# Sema.net
KiCad netlist of a schematic drawn in Altium Designer
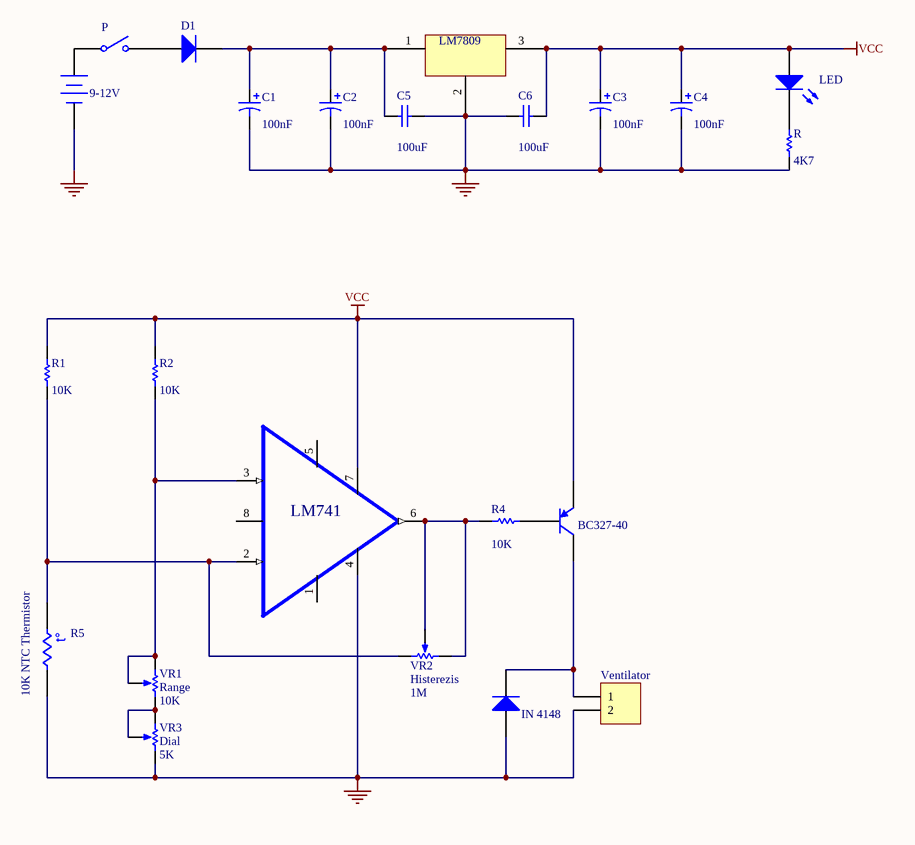
[diagram p0: Sema.SchDoc]

(export (version "E")
  (design (tool "Eeschema 10.0.6"))
  (components
    (comp (ref "9V")
      (value "9-12V")
      (footprint "BAT-2")
      (description "Multicell Battery")
      (fields (field (name "PUBLISHER") "Altium Limited"))
      (libsource (lib "Miscellaneous Devices") (part "Battery"))
    )
    (comp (ref "C1")
      (value "100nF")
      (footprint "CAPPRD350W60D800H1150:CAPPRD350W60D800H1150")
      (description "Polarized Capacitor (Radial)")
      (fields (field (name "Comment") "Cap Pol1") (field (name "PUBLISHER") "Altium Limited"))
      (libsource (lib "Miscellaneous Devices") (part "Cap Pol1"))
    )
    (comp (ref "C2")
      (value "100nF")
      (footprint "CAPPRD350W60D800H1150:CAPPRD350W60D800H1150")
      (description "Polarized Capacitor (Radial)")
      (fields (field (name "Comment") "Cap Pol1") (field (name "PUBLISHER") "Altium Limited"))
      (libsource (lib "Miscellaneous Devices") (part "Cap Pol1"))
    )
    (comp (ref "C3")
      (value "100nF")
      (footprint "CAPPRD350W60D800H1150:CAPPRD350W60D800H1150")
      (description "Polarized Capacitor (Radial)")
      (fields (field (name "Comment") "Cap Pol1") (field (name "PUBLISHER") "Altium Limited"))
      (libsource (lib "Miscellaneous Devices") (part "Cap Pol1"))
    )
    (comp (ref "C4")
      (value "100nF")
      (footprint "CAPPRD350W60D800H1150:CAPPRD350W60D800H1150")
      (description "Polarized Capacitor (Radial)")
      (fields (field (name "Comment") "Cap Pol1") (field (name "PUBLISHER") "Altium Limited"))
      (libsource (lib "Miscellaneous Devices") (part "Cap Pol1"))
    )
    (comp (ref "C5")
      (value "100uF")
      (footprint "RAD-0.1-2")
      (description "Capacitor")
      (fields (field (name "Comment") "Cap") (field (name "PUBLISHER") "Altium Limited"))
      (libsource (lib "Miscellaneous Devices") (part "Cap"))
    )
    (comp (ref "C6")
      (value "100uF")
      (footprint "RAD-0.1-2")
      (description "Capacitor")
      (fields (field (name "Comment") "Cap") (field (name "PUBLISHER") "Altium Limited"))
      (libsource (lib "Miscellaneous Devices") (part "Cap"))
    )
    (comp (ref "D1")
      (value "Diode")
      (footprint "DIOAD1300W80L670D310:DIOAD1300W80L670D310")
      (description "Default Diode")
      (fields (field (name "PUBLISHER") "Altium Limited"))
      (libsource (lib "Miscellaneous Devices") (part "Diode"))
    )
    (comp (ref "D2")
      (value "IN 4148")
      (footprint "DIOAD1300W80L670D310:DIOAD1300W80L670D310")
      (description "Default Diode")
      (fields (field (name "PUBLISHER") "Altium Limited"))
      (libsource (lib "Miscellaneous Devices") (part "Diode"))
    )
    (comp (ref "LED")
      (value "LED")
      (footprint "DIOAD1300W80L670D310:LED-2")
      (description "Typical RED GaAs LED")
      (fields (field (name "PUBLISHER") "Altium Limited"))
      (libsource (lib "Miscellaneous Devices") (part "LED1"))
    )
    (comp (ref "LM741")
      (value "LM741")
      (footprint "DIP254P762X508-8:DIP254P762X508-8")
      (description "General Purpose Amplifier 1 Circuit 8-DIP")
      (fields (field (name "MP") "LM741CN") (field (name "MF") "ON Semiconductor"))
      (libsource (lib "LM741CN") (part "LM741CN"))
    )
    (comp (ref "LM7809")
      (value "LM7809")
      (footprint "TO254P1054X470X2600-3:TO254P1054X470X2600-3")
      (libsource (lib "LM7805") (part "Component_1"))
    )
    (comp (ref "P")
      (value "SW-SPST")
      (footprint "SPST-2")
      (description "Single-Pole, Single-Throw Switch")
      (fields (field (name "PUBLISHER") "Altium Limited"))
      (libsource (lib "Miscellaneous Devices") (part "SW-SPST"))
    )
    (comp (ref "R")
      (value "4K7")
      (footprint "axial-0.4")
      (description "Resistor")
      (fields (field (name "Comment") "Res1") (field (name "PUBLISHER") "Altium Limited"))
      (libsource (lib "Miscellaneous Devices") (part "Res1"))
    )
    (comp (ref "R1")
      (value "10K")
      (footprint "axial-0.4")
      (description "Resistor")
      (fields (field (name "Comment") "Res1") (field (name "PUBLISHER") "Altium Limited"))
      (libsource (lib "Miscellaneous Devices") (part "Res1"))
    )
    (comp (ref "R2")
      (value "10K")
      (footprint "axial-0.4")
      (description "Resistor")
      (fields (field (name "Comment") "Res1") (field (name "PUBLISHER") "Altium Limited"))
      (libsource (lib "Miscellaneous Devices") (part "Res1"))
    )
    (comp (ref "R4")
      (value "10K")
      (footprint "axial-0.4")
      (description "Resistor")
      (fields (field (name "Comment") "Res1") (field (name "PUBLISHER") "Altium Limited"))
      (libsource (lib "Miscellaneous Devices") (part "Res1"))
    )
    (comp (ref "R5")
      (value "10K NTC Thermistor")
      (footprint "RAD-0.1")
      (description "Thermistor")
      (fields (field (name "PUBLISHER") "Altium Limited"))
      (libsource (lib "Miscellaneous Devices") (part "Res Thermal"))
    )
    (comp (ref "Tr")
      (value "BC327-40")
      (footprint "TO-92A")
      (description "PNP General Purpose Amplifier")
      (fields (field (name "PUBLISHER") "Altium Limited"))
      (libsource (lib "Miscellaneous Devices") (part "2N3906"))
    )
    (comp (ref "Ventilator")
      (value "Ventilator")
      (footprint "BAT-2")
      (description "Header, 2-Pin")
      (fields (field (name "PUBLISHER") "Altium Limited"))
      (libsource (lib "Miscellaneous Connectors") (part "Header 2"))
    )
    (comp (ref "VR1")
      (value "Range")
      (footprint "VR5")
      (description "Potentiometer")
      (fields (field (name "ALTIUM_VALUE") "10K") (field (name "PUBLISHER") "Altium Limited"))
      (libsource (lib "Miscellaneous Devices") (part "RPot"))
    )
    (comp (ref "VR2")
      (value "Histerezis")
      (footprint "VR5")
      (description "Potentiometer")
      (fields (field (name "ALTIUM_VALUE") "1M") (field (name "PUBLISHER") "Altium Limited"))
      (libsource (lib "Miscellaneous Devices") (part "RPot"))
    )
    (comp (ref "VR3")
      (value "Dial")
      (footprint "VR5")
      (description "Potentiometer")
      (fields (field (name "ALTIUM_VALUE") "5K") (field (name "PUBLISHER") "Altium Limited"))
      (libsource (lib "Miscellaneous Devices") (part "RPot"))
    )
  )
  (nets
    (net (code "1") (name "GND") (class "Default")
      (node (ref "9V") (pin "2") (pinfunction "-_2") (pintype "passive"))
      (node (ref "C1") (pin "2") (pinfunction "2_2") (pintype "passive"))
      (node (ref "C2") (pin "2") (pinfunction "2_2") (pintype "passive"))
      (node (ref "C3") (pin "2") (pinfunction "2_2") (pintype "passive"))
      (node (ref "C4") (pin "2") (pinfunction "2_2") (pintype "passive"))
      (node (ref "C5") (pin "2") (pinfunction "2_2") (pintype "passive"))
      (node (ref "C6") (pin "1") (pinfunction "1_1") (pintype "passive"))
      (node (ref "D2") (pin "1") (pinfunction "A_1") (pintype "passive"))
      (node (ref "LM741") (pin "4") (pinfunction "V-_4") (pintype "power_in"))
      (node (ref "LM7809") (pin "2") (pinfunction "GND_2") (pintype "passive"))
      (node (ref "R") (pin "1") (pinfunction "1_1") (pintype "passive"))
      (node (ref "R5") (pin "2") (pinfunction "2_2") (pintype "passive"))
      (node (ref "VR3") (pin "3") (pinfunction "BOT_3") (pintype "passive"))
      (node (ref "Ventilator") (pin "2") (pinfunction "2_2") (pintype "passive"))
    )
    (net (code "2") (name "Net-(9V-+)") (class "Default")
      (node (ref "9V") (pin "1") (pinfunction "+_1") (pintype "passive"))
      (node (ref "P") (pin "1") (pinfunction "COMMON_1") (pintype "passive"))
    )
    (net (code "3") (name "Net-(D1-A)") (class "Default")
      (node (ref "D1") (pin "1") (pinfunction "A_1") (pintype "passive"))
      (node (ref "P") (pin "2") (pinfunction "NO_2") (pintype "passive"))
    )
    (net (code "4") (name "Net-(D1-K)") (class "Default")
      (node (ref "C1") (pin "1") (pinfunction "1_1") (pintype "passive"))
      (node (ref "C2") (pin "1") (pinfunction "1_1") (pintype "passive"))
      (node (ref "C5") (pin "1") (pinfunction "1_1") (pintype "passive"))
      (node (ref "D1") (pin "2") (pinfunction "K_2") (pintype "passive"))
      (node (ref "LM7809") (pin "1") (pinfunction "OF2_1") (pintype "passive"))
    )
    (net (code "5") (name "Net-(D2-K)") (class "Default")
      (node (ref "D2") (pin "2") (pinfunction "K_2") (pintype "passive"))
      (node (ref "Tr") (pin "1") (pinfunction "C_1") (pintype "passive"))
      (node (ref "Ventilator") (pin "1") (pinfunction "1_1") (pintype "passive"))
    )
    (net (code "6") (name "Net-(LED-K)") (class "Default")
      (node (ref "LED") (pin "2") (pinfunction "K_2") (pintype "passive"))
      (node (ref "R") (pin "2") (pinfunction "2_2") (pintype "passive"))
    )
    (net (code "7") (name "Net-(LM741-NEG)") (class "Default")
      (node (ref "LM741") (pin "2") (pinfunction "NEG_2") (pintype "input"))
      (node (ref "R1") (pin "1") (pinfunction "1_1") (pintype "passive"))
      (node (ref "R5") (pin "1") (pinfunction "1_1") (pintype "passive"))
      (node (ref "VR2") (pin "3") (pinfunction "BOT_3") (pintype "passive"))
    )
    (net (code "8") (name "Net-(LM741-OUT)") (class "Default")
      (node (ref "LM741") (pin "6") (pinfunction "OUT_6") (pintype "output"))
      (node (ref "R4") (pin "2") (pinfunction "2_2") (pintype "passive"))
      (node (ref "VR2") (pin "1") (pinfunction "TOP_1") (pintype "passive"))
      (node (ref "VR2") (pin "2") (pinfunction "TAP_2") (pintype "passive"))
    )
    (net (code "9") (name "Net-(LM741-POS)") (class "Default")
      (node (ref "LM741") (pin "3") (pinfunction "POS_3") (pintype "input"))
      (node (ref "R2") (pin "1") (pinfunction "1_1") (pintype "passive"))
      (node (ref "VR1") (pin "1") (pinfunction "TOP_1") (pintype "passive"))
      (node (ref "VR1") (pin "2") (pinfunction "TAP_2") (pintype "passive"))
    )
    (net (code "10") (name "Net-(Tr-B)") (class "Default")
      (node (ref "R4") (pin "1") (pinfunction "1_1") (pintype "passive"))
      (node (ref "Tr") (pin "2") (pinfunction "B_2") (pintype "passive"))
    )
    (net (code "11") (name "Net-(VR1-BOT)") (class "Default")
      (node (ref "VR1") (pin "3") (pinfunction "BOT_3") (pintype "passive"))
      (node (ref "VR3") (pin "1") (pinfunction "TOP_1") (pintype "passive"))
      (node (ref "VR3") (pin "2") (pinfunction "TAP_2") (pintype "passive"))
    )
    (net (code "12") (name "VCC") (class "Default")
      (node (ref "C3") (pin "1") (pinfunction "1_1") (pintype "passive"))
      (node (ref "C4") (pin "1") (pinfunction "1_1") (pintype "passive"))
      (node (ref "C6") (pin "2") (pinfunction "2_2") (pintype "passive"))
      (node (ref "LED") (pin "1") (pinfunction "A_1") (pintype "passive"))
      (node (ref "LM741") (pin "7") (pinfunction "V+_7") (pintype "power_in"))
      (node (ref "LM7809") (pin "3") (pinfunction "POS_3") (pintype "passive"))
      (node (ref "R1") (pin "2") (pinfunction "2_2") (pintype "passive"))
      (node (ref "R2") (pin "2") (pinfunction "2_2") (pintype "passive"))
      (node (ref "Tr") (pin "3") (pinfunction "E_3") (pintype "passive"))
    )
    (net (code "13") (name "unconnected-(LM741-NC-Pad8)") (class "Default")
      (node (ref "LM741") (pin "8") (pinfunction "NC_8") (pintype "passive"))
    )
    (net (code "14") (name "unconnected-(LM741-OF1-Pad5)") (class "Default")
      (node (ref "LM741") (pin "5") (pinfunction "OF1_5") (pintype "passive"))
    )
    (net (code "15") (name "unconnected-(LM741-OF2-Pad1)") (class "Default")
      (node (ref "LM741") (pin "1") (pinfunction "OF2_1") (pintype "passive"))
    )
  )
)
